# AutoDriver_Shield.net
KiCad netlist of a schematic drawn in EAGLE
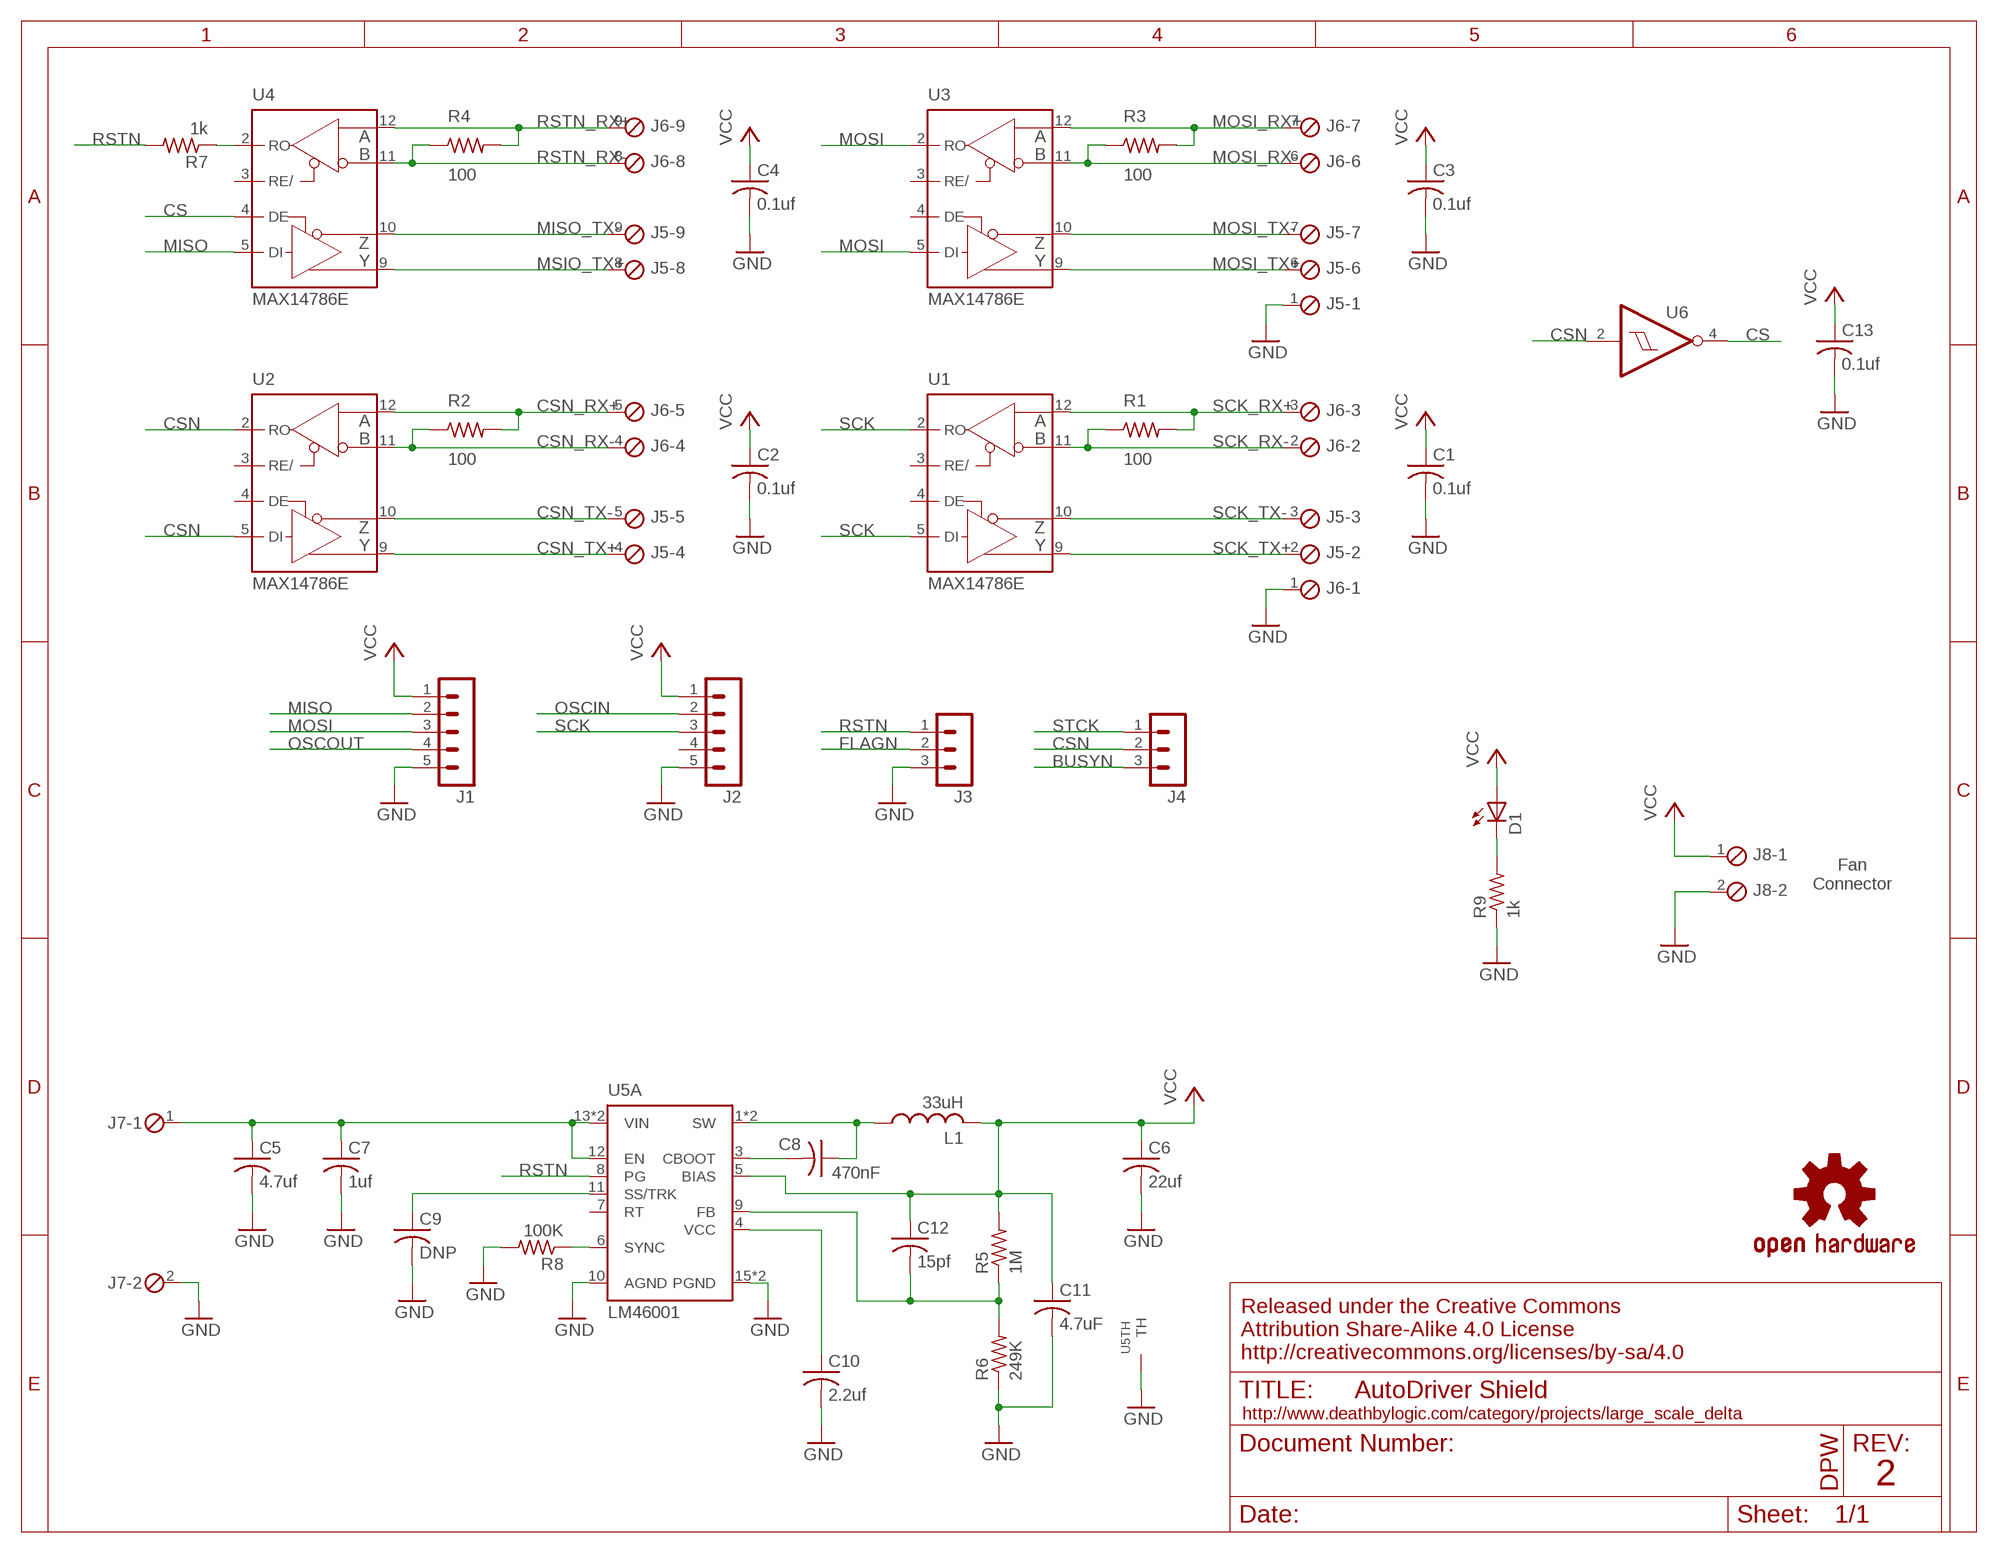
[diagram p0: schematic, sheet 1]

(export (version "E")
  (design (tool "Eeschema 10.0.6"))
  (components
    (comp (ref "C1")
      (value "0.1uf")
      (footprint "eagle-import:C0805K")
      (libsource (lib "eagle-import") (part "C-USC0805K"))
    )
    (comp (ref "C2")
      (value "0.1uf")
      (footprint "eagle-import:C0805K")
      (libsource (lib "eagle-import") (part "C-USC0805K"))
    )
    (comp (ref "C3")
      (value "0.1uf")
      (footprint "eagle-import:C0805K")
      (libsource (lib "eagle-import") (part "C-USC0805K"))
    )
    (comp (ref "C4")
      (value "0.1uf")
      (footprint "eagle-import:C0805K")
      (libsource (lib "eagle-import") (part "C-USC0805K"))
    )
    (comp (ref "C5")
      (value "4.7uf")
      (footprint "eagle-import:C1210K")
      (libsource (lib "eagle-import") (part "C-USC1210K"))
    )
    (comp (ref "C6")
      (value "22uf")
      (footprint "eagle-import:C1210K")
      (libsource (lib "eagle-import") (part "C-USC1210K"))
    )
    (comp (ref "C7")
      (value "1uf")
      (footprint "eagle-import:C1206K")
      (libsource (lib "eagle-import") (part "C-USC1206K"))
    )
    (comp (ref "C8")
      (value "470nF")
      (footprint "eagle-import:C0805K")
      (libsource (lib "eagle-import") (part "C-USC0805K"))
    )
    (comp (ref "C9")
      (value "DNP")
      (footprint "eagle-import:C0603K")
      (libsource (lib "eagle-import") (part "C-USC0603K"))
    )
    (comp (ref "C10")
      (value "2.2uf")
      (footprint "eagle-import:C0603K")
      (libsource (lib "eagle-import") (part "C-USC0603K"))
    )
    (comp (ref "C11")
      (value "4.7uF")
      (footprint "eagle-import:C0805K")
      (libsource (lib "eagle-import") (part "C-USC0805K"))
    )
    (comp (ref "C12")
      (value "15pf")
      (footprint "eagle-import:C0805K")
      (libsource (lib "eagle-import") (part "C-USC0805K"))
    )
    (comp (ref "C13")
      (value "0.1uf")
      (footprint "eagle-import:C0805K")
      (libsource (lib "eagle-import") (part "C-USC0805K"))
    )
    (comp (ref "D1")
      (value "LEDCHIPLED_0805")
      (footprint "eagle-import:CHIPLED_0805")
      (libsource (lib "eagle-import") (part "LEDCHIPLED_0805"))
    )
    (comp (ref "J1")
      (value "MA05-1")
      (footprint "eagle-import:MA05-1")
      (libsource (lib "eagle-import") (part "MA05-1"))
    )
    (comp (ref "J2")
      (value "MA05-1")
      (footprint "eagle-import:MA05-1")
      (libsource (lib "eagle-import") (part "MA05-1"))
    )
    (comp (ref "J3")
      (value "MA03-1")
      (footprint "eagle-import:MA03-1")
      (libsource (lib "eagle-import") (part "MA03-1"))
    )
    (comp (ref "J4")
      (value "MA03-1")
      (footprint "eagle-import:MA03-1")
      (libsource (lib "eagle-import") (part "MA03-1"))
    )
    (comp (ref "J5")
      (value "MPT9")
      (footprint "eagle-import:9POL254")
      (libsource (lib "eagle-import") (part "MPT9"))
    )
    (comp (ref "J6")
      (value "MPT9")
      (footprint "eagle-import:9POL254")
      (libsource (lib "eagle-import") (part "MPT9"))
    )
    (comp (ref "J7")
      (value "MPT2")
      (footprint "eagle-import:2POL254")
      (libsource (lib "eagle-import") (part "MPT2"))
    )
    (comp (ref "J8")
      (value "MPT2")
      (footprint "eagle-import:2POL254")
      (libsource (lib "eagle-import") (part "MPT2"))
    )
    (comp (ref "L1")
      (value "33uH")
      (footprint "eagle-import:L6045")
      (libsource (lib "eagle-import") (part "SRN6045"))
    )
    (comp (ref "LOGO1")
      (value "OSHW-LOGOM")
      (footprint "eagle-import:OSHW-LOGO-M")
      (libsource (lib "eagle-import") (part "OSHW-LOGOM"))
    )
    (comp (ref "R1")
      (value "100")
      (footprint "eagle-import:R1206")
      (libsource (lib "eagle-import") (part "R-US_R1206"))
    )
    (comp (ref "R2")
      (value "100")
      (footprint "eagle-import:R1206")
      (libsource (lib "eagle-import") (part "R-US_R1206"))
    )
    (comp (ref "R3")
      (value "100")
      (footprint "eagle-import:R1206")
      (libsource (lib "eagle-import") (part "R-US_R1206"))
    )
    (comp (ref "R4")
      (value "100")
      (footprint "eagle-import:R1206")
      (libsource (lib "eagle-import") (part "R-US_R1206"))
    )
    (comp (ref "R5")
      (value "1M")
      (footprint "eagle-import:R0402")
      (libsource (lib "eagle-import") (part "resistor_R-US_R0402"))
    )
    (comp (ref "R6")
      (value "249K")
      (footprint "eagle-import:R0402")
      (libsource (lib "eagle-import") (part "resistor_R-US_R0402"))
    )
    (comp (ref "R7")
      (value "1k")
      (footprint "eagle-import:R0805")
      (libsource (lib "eagle-import") (part "R-US_R0805"))
    )
    (comp (ref "R8")
      (value "100K")
      (footprint "eagle-import:R0402")
      (libsource (lib "eagle-import") (part "resistor_R-US_R0402"))
    )
    (comp (ref "R9")
      (value "1k")
      (footprint "eagle-import:R0805")
      (libsource (lib "eagle-import") (part "R-US_R0805"))
    )
    (comp (ref "U$2")
      (value "PENGUIN_LOGOSILKSCREEN")
      (footprint "eagle-import:PENGUIN_SILKSCREEN")
      (libsource (lib "eagle-import") (part "PENGUIN_LOGOSILKSCREEN"))
    )
    (comp (ref "U1")
      (value "MAX14786E")
      (footprint "eagle-import:SO14")
      (fields (field (name "MF") "MAXIM") (field (name "MPN") "MAX489CSD"))
      (libsource (lib "eagle-import") (part "MAX489CSD"))
    )
    (comp (ref "U2")
      (value "MAX14786E")
      (footprint "eagle-import:SO14")
      (fields (field (name "MF") "MAXIM") (field (name "MPN") "MAX489CSD"))
      (libsource (lib "eagle-import") (part "MAX489CSD"))
    )
    (comp (ref "U3")
      (value "MAX14786E")
      (footprint "eagle-import:SO14")
      (fields (field (name "MF") "MAXIM") (field (name "MPN") "MAX489CSD"))
      (libsource (lib "eagle-import") (part "MAX489CSD"))
    )
    (comp (ref "U4")
      (value "MAX14786E")
      (footprint "eagle-import:SO14")
      (fields (field (name "MF") "MAXIM") (field (name "MPN") "MAX489CSD"))
      (libsource (lib "eagle-import") (part "MAX489CSD"))
    )
    (comp (ref "U5")
      (value "LM46001")
      (footprint "eagle-import:HTSSOP16PWP")
      (libsource (lib "eagle-import") (part "LM46001"))
    )
    (comp (ref "U6")
      (value "74AHC1G14")
      (footprint "eagle-import:SOT23-5")
      (libsource (lib "eagle-import") (part "741G14DBVAHC"))
    )
  )
  (nets
    (net (code "1") (name "/BUSYN") (class "Default")
      (node (ref "J4") (pin "3") (pinfunction "3_3") (pintype "passive"))
    )
    (net (code "2") (name "/CS") (class "Default")
      (node (ref "U4") (pin "4") (pinfunction "DE_4") (pintype "input"))
      (node (ref "U6") (pin "4") (pinfunction "O_4") (pintype "output"))
    )
    (net (code "3") (name "/CSN") (class "Default")
      (node (ref "J4") (pin "2") (pinfunction "2_2") (pintype "passive"))
      (node (ref "U2") (pin "2") (pinfunction "RO_2") (pintype "output"))
      (node (ref "U2") (pin "5") (pinfunction "DI_5") (pintype "input"))
      (node (ref "U6") (pin "2") (pinfunction "I_2") (pintype "input"))
    )
    (net (code "4") (name "/CSN_RX+") (class "Default")
      (node (ref "J6") (pin "5") (pinfunction "1_5") (pintype "passive"))
      (node (ref "R2") (pin "2") (pinfunction "2_2") (pintype "passive"))
      (node (ref "U2") (pin "12") (pinfunction "A_12") (pintype "passive"))
    )
    (net (code "5") (name "/CSN_RX-") (class "Default")
      (node (ref "J6") (pin "4") (pinfunction "1_4") (pintype "passive"))
      (node (ref "R2") (pin "1") (pinfunction "1_1") (pintype "passive"))
      (node (ref "U2") (pin "11") (pinfunction "B_11") (pintype "passive"))
    )
    (net (code "6") (name "/CSN_TX+") (class "Default")
      (node (ref "J5") (pin "4") (pinfunction "1_4") (pintype "passive"))
      (node (ref "U2") (pin "9") (pinfunction "Y_9") (pintype "passive"))
    )
    (net (code "7") (name "/CSN_TX-") (class "Default")
      (node (ref "J5") (pin "5") (pinfunction "1_5") (pintype "passive"))
      (node (ref "U2") (pin "10") (pinfunction "Z_10") (pintype "passive"))
    )
    (net (code "8") (name "/FLAGN") (class "Default")
      (node (ref "J3") (pin "2") (pinfunction "2_2") (pintype "passive"))
    )
    (net (code "9") (name "/MISO") (class "Default")
      (node (ref "J1") (pin "2") (pinfunction "2_2") (pintype "passive"))
      (node (ref "U4") (pin "5") (pinfunction "DI_5") (pintype "input"))
    )
    (net (code "10") (name "/MISO_TX-") (class "Default")
      (node (ref "J5") (pin "9") (pinfunction "1_9") (pintype "passive"))
      (node (ref "U4") (pin "10") (pinfunction "Z_10") (pintype "passive"))
    )
    (net (code "11") (name "/MOSI") (class "Default")
      (node (ref "J1") (pin "3") (pinfunction "3_3") (pintype "passive"))
      (node (ref "U3") (pin "2") (pinfunction "RO_2") (pintype "output"))
      (node (ref "U3") (pin "5") (pinfunction "DI_5") (pintype "input"))
    )
    (net (code "12") (name "/MOSI_RX+") (class "Default")
      (node (ref "J6") (pin "7") (pinfunction "1_7") (pintype "passive"))
      (node (ref "R3") (pin "2") (pinfunction "2_2") (pintype "passive"))
      (node (ref "U3") (pin "12") (pinfunction "A_12") (pintype "passive"))
    )
    (net (code "13") (name "/MOSI_RX-") (class "Default")
      (node (ref "J6") (pin "6") (pinfunction "1_6") (pintype "passive"))
      (node (ref "R3") (pin "1") (pinfunction "1_1") (pintype "passive"))
      (node (ref "U3") (pin "11") (pinfunction "B_11") (pintype "passive"))
    )
    (net (code "14") (name "/MOSI_TX+") (class "Default")
      (node (ref "J5") (pin "6") (pinfunction "1_6") (pintype "passive"))
      (node (ref "U3") (pin "9") (pinfunction "Y_9") (pintype "passive"))
    )
    (net (code "15") (name "/MOSI_TX-") (class "Default")
      (node (ref "J5") (pin "7") (pinfunction "1_7") (pintype "passive"))
      (node (ref "U3") (pin "10") (pinfunction "Z_10") (pintype "passive"))
    )
    (net (code "16") (name "/MSIO_TX+") (class "Default")
      (node (ref "J5") (pin "8") (pinfunction "1_8") (pintype "passive"))
      (node (ref "U4") (pin "9") (pinfunction "Y_9") (pintype "passive"))
    )
    (net (code "17") (name "/OSCIN") (class "Default")
      (node (ref "J2") (pin "2") (pinfunction "2_2") (pintype "passive"))
    )
    (net (code "18") (name "/OSCOUT") (class "Default")
      (node (ref "J1") (pin "4") (pinfunction "4_4") (pintype "passive"))
    )
    (net (code "19") (name "/RSTN") (class "Default")
      (node (ref "J3") (pin "1") (pinfunction "1_1") (pintype "passive"))
      (node (ref "R7") (pin "2") (pinfunction "2_2") (pintype "passive"))
      (node (ref "U5") (pin "8") (pinfunction "PG_8") (pintype "input"))
    )
    (net (code "20") (name "/RSTN_RX+") (class "Default")
      (node (ref "J6") (pin "9") (pinfunction "1_9") (pintype "passive"))
      (node (ref "R4") (pin "2") (pinfunction "2_2") (pintype "passive"))
      (node (ref "U4") (pin "12") (pinfunction "A_12") (pintype "passive"))
    )
    (net (code "21") (name "/RSTN_RX-") (class "Default")
      (node (ref "J6") (pin "8") (pinfunction "1_8") (pintype "passive"))
      (node (ref "R4") (pin "1") (pinfunction "1_1") (pintype "passive"))
      (node (ref "U4") (pin "11") (pinfunction "B_11") (pintype "passive"))
    )
    (net (code "22") (name "/SCK") (class "Default")
      (node (ref "J2") (pin "3") (pinfunction "3_3") (pintype "passive"))
      (node (ref "U1") (pin "2") (pinfunction "RO_2") (pintype "output"))
      (node (ref "U1") (pin "5") (pinfunction "DI_5") (pintype "input"))
    )
    (net (code "23") (name "/SCK_RX+") (class "Default")
      (node (ref "J6") (pin "3") (pinfunction "1_3") (pintype "passive"))
      (node (ref "R1") (pin "2") (pinfunction "2_2") (pintype "passive"))
      (node (ref "U1") (pin "12") (pinfunction "A_12") (pintype "passive"))
    )
    (net (code "24") (name "/SCK_RX-") (class "Default")
      (node (ref "J6") (pin "2") (pinfunction "1_2") (pintype "passive"))
      (node (ref "R1") (pin "1") (pinfunction "1_1") (pintype "passive"))
      (node (ref "U1") (pin "11") (pinfunction "B_11") (pintype "passive"))
    )
    (net (code "25") (name "/SCK_TX+") (class "Default")
      (node (ref "J5") (pin "2") (pinfunction "1_2") (pintype "passive"))
      (node (ref "U1") (pin "9") (pinfunction "Y_9") (pintype "passive"))
    )
    (net (code "26") (name "/SCK_TX-") (class "Default")
      (node (ref "J5") (pin "3") (pinfunction "1_3") (pintype "passive"))
      (node (ref "U1") (pin "10") (pinfunction "Z_10") (pintype "passive"))
    )
    (net (code "27") (name "/STCK") (class "Default")
      (node (ref "J4") (pin "1") (pinfunction "1_1") (pintype "passive"))
    )
    (net (code "28") (name "GND") (class "Default")
      (node (ref "C1") (pin "2") (pinfunction "2_2") (pintype "passive"))
      (node (ref "C10") (pin "2") (pinfunction "2_2") (pintype "passive"))
      (node (ref "C11") (pin "2") (pinfunction "2_2") (pintype "passive"))
      (node (ref "C13") (pin "2") (pinfunction "2_2") (pintype "passive"))
      (node (ref "C2") (pin "2") (pinfunction "2_2") (pintype "passive"))
      (node (ref "C3") (pin "2") (pinfunction "2_2") (pintype "passive"))
      (node (ref "C4") (pin "2") (pinfunction "2_2") (pintype "passive"))
      (node (ref "C5") (pin "2") (pinfunction "2_2") (pintype "passive"))
      (node (ref "C6") (pin "2") (pinfunction "2_2") (pintype "passive"))
      (node (ref "C7") (pin "2") (pinfunction "2_2") (pintype "passive"))
      (node (ref "C9") (pin "2") (pinfunction "2_2") (pintype "passive"))
      (node (ref "J1") (pin "5") (pinfunction "5_5") (pintype "passive"))
      (node (ref "J2") (pin "5") (pinfunction "5_5") (pintype "passive"))
      (node (ref "J3") (pin "3") (pinfunction "3_3") (pintype "passive"))
      (node (ref "J5") (pin "1") (pinfunction "1_1") (pintype "passive"))
      (node (ref "J6") (pin "1") (pinfunction "1_1") (pintype "passive"))
      (node (ref "J7") (pin "2") (pinfunction "1_2") (pintype "passive"))
      (node (ref "J8") (pin "2") (pinfunction "1_2") (pintype "passive"))
      (node (ref "R6") (pin "1") (pinfunction "1_1") (pintype "passive"))
      (node (ref "R8") (pin "2") (pinfunction "2_2") (pintype "passive"))
      (node (ref "R9") (pin "1") (pinfunction "1_1") (pintype "passive"))
      (node (ref "U5") (pin "10") (pinfunction "AGND_10") (pintype "power_in"))
      (node (ref "U5") (pin "15") (pinfunction "PGND_15") (pintype "power_in"))
      (node (ref "U5") (pin "16") (pinfunction "PGND_16") (pintype "power_in"))
      (node (ref "U5") (pin "TH1") (pinfunction "TH_TH1") (pintype "passive"))
      (node (ref "U5") (pin "TH10") (pinfunction "TH_TH10") (pintype "passive"))
      (node (ref "U5") (pin "TH11") (pinfunction "TH_TH11") (pintype "passive"))
      (node (ref "U5") (pin "TH12") (pinfunction "TH_TH12") (pintype "passive"))
      (node (ref "U5") (pin "TH2") (pinfunction "TH_TH2") (pintype "passive"))
      (node (ref "U5") (pin "TH3") (pinfunction "TH_TH3") (pintype "passive"))
      (node (ref "U5") (pin "TH4") (pinfunction "TH_TH4") (pintype "passive"))
      (node (ref "U5") (pin "TH5") (pinfunction "TH_TH5") (pintype "passive"))
      (node (ref "U5") (pin "TH6") (pinfunction "TH_TH6") (pintype "passive"))
      (node (ref "U5") (pin "TH7") (pinfunction "TH_TH7") (pintype "passive"))
      (node (ref "U5") (pin "TH8") (pinfunction "TH_TH8") (pintype "passive"))
      (node (ref "U5") (pin "TH9") (pinfunction "TH_TH9") (pintype "passive"))
      (node (ref "U5") (pin "THA") (pinfunction "TH_THA") (pintype "passive"))
      (node (ref "U5") (pin "THB") (pinfunction "TH_THB") (pintype "passive"))
    )
    (net (code "29") (name "Net-(D1-PadC)") (class "Default")
      (node (ref "D1") (pin "C") (pinfunction "C_C") (pintype "passive"))
      (node (ref "R9") (pin "2") (pinfunction "2_2") (pintype "passive"))
    )
    (net (code "30") (name "Net-(L1-1)") (class "Default")
      (node (ref "C8") (pin "1") (pinfunction "1_1") (pintype "passive"))
      (node (ref "L1") (pin "P$1") (pinfunction "1_P$1") (pintype "passive"))
      (node (ref "U5") (pin "1") (pinfunction "SW_1") (pintype "passive"))
      (node (ref "U5") (pin "2") (pinfunction "SW_2") (pintype "passive"))
    )
    (net (code "31") (name "Net-(U4D-RO)") (class "Default")
      (node (ref "R7") (pin "1") (pinfunction "1_1") (pintype "passive"))
      (node (ref "U4") (pin "2") (pinfunction "RO_2") (pintype "output"))
    )
    (net (code "32") (name "Net-(U5A-CBOOT)") (class "Default")
      (node (ref "C8") (pin "2") (pinfunction "2_2") (pintype "passive"))
      (node (ref "U5") (pin "3") (pinfunction "CBOOT_3") (pintype "passive"))
    )
    (net (code "33") (name "Net-(U5A-EN)") (class "Default")
      (node (ref "C5") (pin "1") (pinfunction "1_1") (pintype "passive"))
      (node (ref "C7") (pin "1") (pinfunction "1_1") (pintype "passive"))
      (node (ref "J7") (pin "1") (pinfunction "1_1") (pintype "passive"))
      (node (ref "U5") (pin "12") (pinfunction "EN_12") (pintype "input"))
      (node (ref "U5") (pin "13") (pinfunction "VIN_13") (pintype "input"))
      (node (ref "U5") (pin "14") (pinfunction "VIN_14") (pintype "input"))
    )
    (net (code "34") (name "Net-(U5A-FB)") (class "Default")
      (node (ref "C12") (pin "2") (pinfunction "2_2") (pintype "passive"))
      (node (ref "R5") (pin "1") (pinfunction "1_1") (pintype "passive"))
      (node (ref "R6") (pin "2") (pinfunction "2_2") (pintype "passive"))
      (node (ref "U5") (pin "9") (pinfunction "FB_9") (pintype "input"))
    )
    (net (code "35") (name "Net-(U5A-SS{slash}TRK)") (class "Default")
      (node (ref "C9") (pin "1") (pinfunction "1_1") (pintype "passive"))
      (node (ref "U5") (pin "11") (pinfunction "SS/TRK_11") (pintype "input"))
    )
    (net (code "36") (name "Net-(U5A-SYNC)") (class "Default")
      (node (ref "R8") (pin "1") (pinfunction "1_1") (pintype "passive"))
      (node (ref "U5") (pin "6") (pinfunction "SYNC_6") (pintype "input"))
    )
    (net (code "37") (name "Net-(U5A-VCC)") (class "Default")
      (node (ref "C10") (pin "1") (pinfunction "1_1") (pintype "passive"))
      (node (ref "U5") (pin "4") (pinfunction "VCC_4") (pintype "output"))
    )
    (net (code "38") (name "VCC") (class "Default")
      (node (ref "C1") (pin "1") (pinfunction "1_1") (pintype "passive"))
      (node (ref "C11") (pin "1") (pinfunction "1_1") (pintype "passive"))
      (node (ref "C12") (pin "1") (pinfunction "1_1") (pintype "passive"))
      (node (ref "C13") (pin "1") (pinfunction "1_1") (pintype "passive"))
      (node (ref "C2") (pin "1") (pinfunction "1_1") (pintype "passive"))
      (node (ref "C3") (pin "1") (pinfunction "1_1") (pintype "passive"))
      (node (ref "C4") (pin "1") (pinfunction "1_1") (pintype "passive"))
      (node (ref "C6") (pin "1") (pinfunction "1_1") (pintype "passive"))
      (node (ref "D1") (pin "A") (pinfunction "A_A") (pintype "passive"))
      (node (ref "J1") (pin "1") (pinfunction "1_1") (pintype "passive"))
      (node (ref "J2") (pin "1") (pinfunction "1_1") (pintype "passive"))
      (node (ref "J8") (pin "1") (pinfunction "1_1") (pintype "passive"))
      (node (ref "L1") (pin "P$2") (pinfunction "2_P$2") (pintype "passive"))
      (node (ref "R5") (pin "2") (pinfunction "2_2") (pintype "passive"))
      (node (ref "U5") (pin "5") (pinfunction "BIAS_5") (pintype "input"))
    )
    (net (code "39") (name "unconnected-(J2-Pad4)") (class "Default")
      (node (ref "J2") (pin "4") (pinfunction "4_4") (pintype "passive"))
    )
    (net (code "40") (name "unconnected-(U1D-DE-Pad4)") (class "Default")
      (node (ref "U1") (pin "4") (pinfunction "DE_4") (pintype "input"))
    )
    (net (code "41") (name "unconnected-(U1D-RE{slash}-Pad3)") (class "Default")
      (node (ref "U1") (pin "3") (pinfunction "RE/_3") (pintype "input"))
    )
    (net (code "42") (name "unconnected-(U2D-DE-Pad4)") (class "Default")
      (node (ref "U2") (pin "4") (pinfunction "DE_4") (pintype "input"))
    )
    (net (code "43") (name "unconnected-(U2D-RE{slash}-Pad3)") (class "Default")
      (node (ref "U2") (pin "3") (pinfunction "RE/_3") (pintype "input"))
    )
    (net (code "44") (name "unconnected-(U3D-DE-Pad4)") (class "Default")
      (node (ref "U3") (pin "4") (pinfunction "DE_4") (pintype "input"))
    )
    (net (code "45") (name "unconnected-(U3D-RE{slash}-Pad3)") (class "Default")
      (node (ref "U3") (pin "3") (pinfunction "RE/_3") (pintype "input"))
    )
    (net (code "46") (name "unconnected-(U4D-RE{slash}-Pad3)") (class "Default")
      (node (ref "U4") (pin "3") (pinfunction "RE/_3") (pintype "input"))
    )
    (net (code "47") (name "unconnected-(U5A-RT-Pad7)") (class "Default")
      (node (ref "U5") (pin "7") (pinfunction "RT_7") (pintype "input"))
    )
  )
)
